# main.net
KiCad netlist of a schematic drawn in Altium Designer
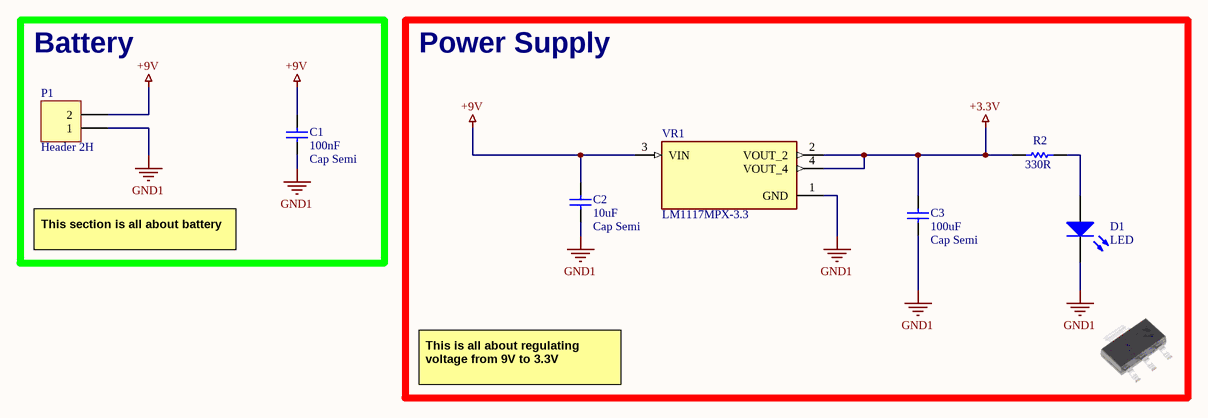
[diagram p0: main.SchDoc]

(export (version "E")
  (design (tool "Eeschema 10.0.6"))
  (components
    (comp (ref "C1")
      (value "Cap Semi")
      (footprint "C1206")
      (description "Capacitor (Semiconductor SIM Model)")
      (fields (field (name "ALTIUM_VALUE") "100nF") (field (name "PUBLISHER") "Altium Limited"))
      (libsource (lib "Miscellaneous Devices") (part "Cap Semi"))
    )
    (comp (ref "C2")
      (value "Cap Semi")
      (footprint "C1206")
      (description "Capacitor (Semiconductor SIM Model)")
      (fields (field (name "ALTIUM_VALUE") "10uF") (field (name "PUBLISHER") "Altium Limited"))
      (libsource (lib "Miscellaneous Devices") (part "Cap Semi"))
    )
    (comp (ref "C3")
      (value "Cap Semi")
      (footprint "C1206")
      (description "Capacitor (Semiconductor SIM Model)")
      (fields (field (name "ALTIUM_VALUE") "100uF") (field (name "PUBLISHER") "Altium Limited"))
      (libsource (lib "Miscellaneous Devices") (part "Cap Semi"))
    )
    (comp (ref "D1")
      (value "LED")
      (footprint "MY_LED_0805")
      (description "Typical INFRARED GaAs LED")
      (fields (field (name "ASID PART NUMBER") "LED-AS"))
      (libsource (lib "003 Mylib-Rev-4") (part "LED"))
    )
    (comp (ref "P1")
      (value "Header 2H")
      (footprint "HDR1X2H")
      (description "Header, 2-Pin, Right Angle")
      (fields (field (name "PUBLISHER") "Altium Limited"))
      (libsource (lib "Miscellaneous Connectors") (part "Header 2H"))
    )
    (comp (ref "R2")
      (value "330R")
      (footprint "MY_0805")
      (description "Standard resistor")
      (fields (field (name "ASID PART NUMBER") "Res-AS"))
      (libsource (lib "003 Mylib-Rev-4") (part "Res"))
    )
    (comp (ref "VR1")
      (value "LM1117MPX-3.3")
      (footprint "VREG_LM1117MPX-3.3")
      (description "800-mA 15-V linear voltage regulator")
      (fields (field (name "MF") "Texas Instruments"))
      (libsource (lib "LM1117MPX-3.3") (part "LM1117MPX-3.3"))
    )
  )
  (nets
    (net (code "1") (name "+3.3V") (class "Default")
      (node (ref "C3") (pin "2") (pinfunction "2_2") (pintype "passive"))
      (node (ref "R2") (pin "1") (pinfunction "1_1") (pintype "passive"))
      (node (ref "VR1") (pin "2") (pinfunction "VOUT_2_2") (pintype "output"))
      (node (ref "VR1") (pin "4") (pinfunction "VOUT_4_4") (pintype "output"))
    )
    (net (code "2") (name "+9V") (class "Default")
      (node (ref "C1") (pin "2") (pinfunction "2_2") (pintype "passive"))
      (node (ref "C2") (pin "2") (pinfunction "2_2") (pintype "passive"))
      (node (ref "P1") (pin "2") (pinfunction "2_2") (pintype "passive"))
      (node (ref "VR1") (pin "3") (pinfunction "VIN_3") (pintype "input"))
    )
    (net (code "3") (name "GND1") (class "Default")
      (node (ref "C1") (pin "1") (pinfunction "1_1") (pintype "passive"))
      (node (ref "C2") (pin "1") (pinfunction "1_1") (pintype "passive"))
      (node (ref "C3") (pin "1") (pinfunction "1_1") (pintype "passive"))
      (node (ref "D1") (pin "K") (pinfunction "K_K") (pintype "passive"))
      (node (ref "P1") (pin "1") (pinfunction "1_1") (pintype "passive"))
      (node (ref "VR1") (pin "1") (pinfunction "GND_1") (pintype "power_in"))
    )
    (net (code "4") (name "Net-(D1-PadA)") (class "Default")
      (node (ref "D1") (pin "A") (pinfunction "A_A") (pintype "passive"))
      (node (ref "R2") (pin "2") (pinfunction "2_2") (pintype "passive"))
    )
  )
)
